# new_boardforfirebot.net
KiCad netlist of a schematic drawn in EAGLE
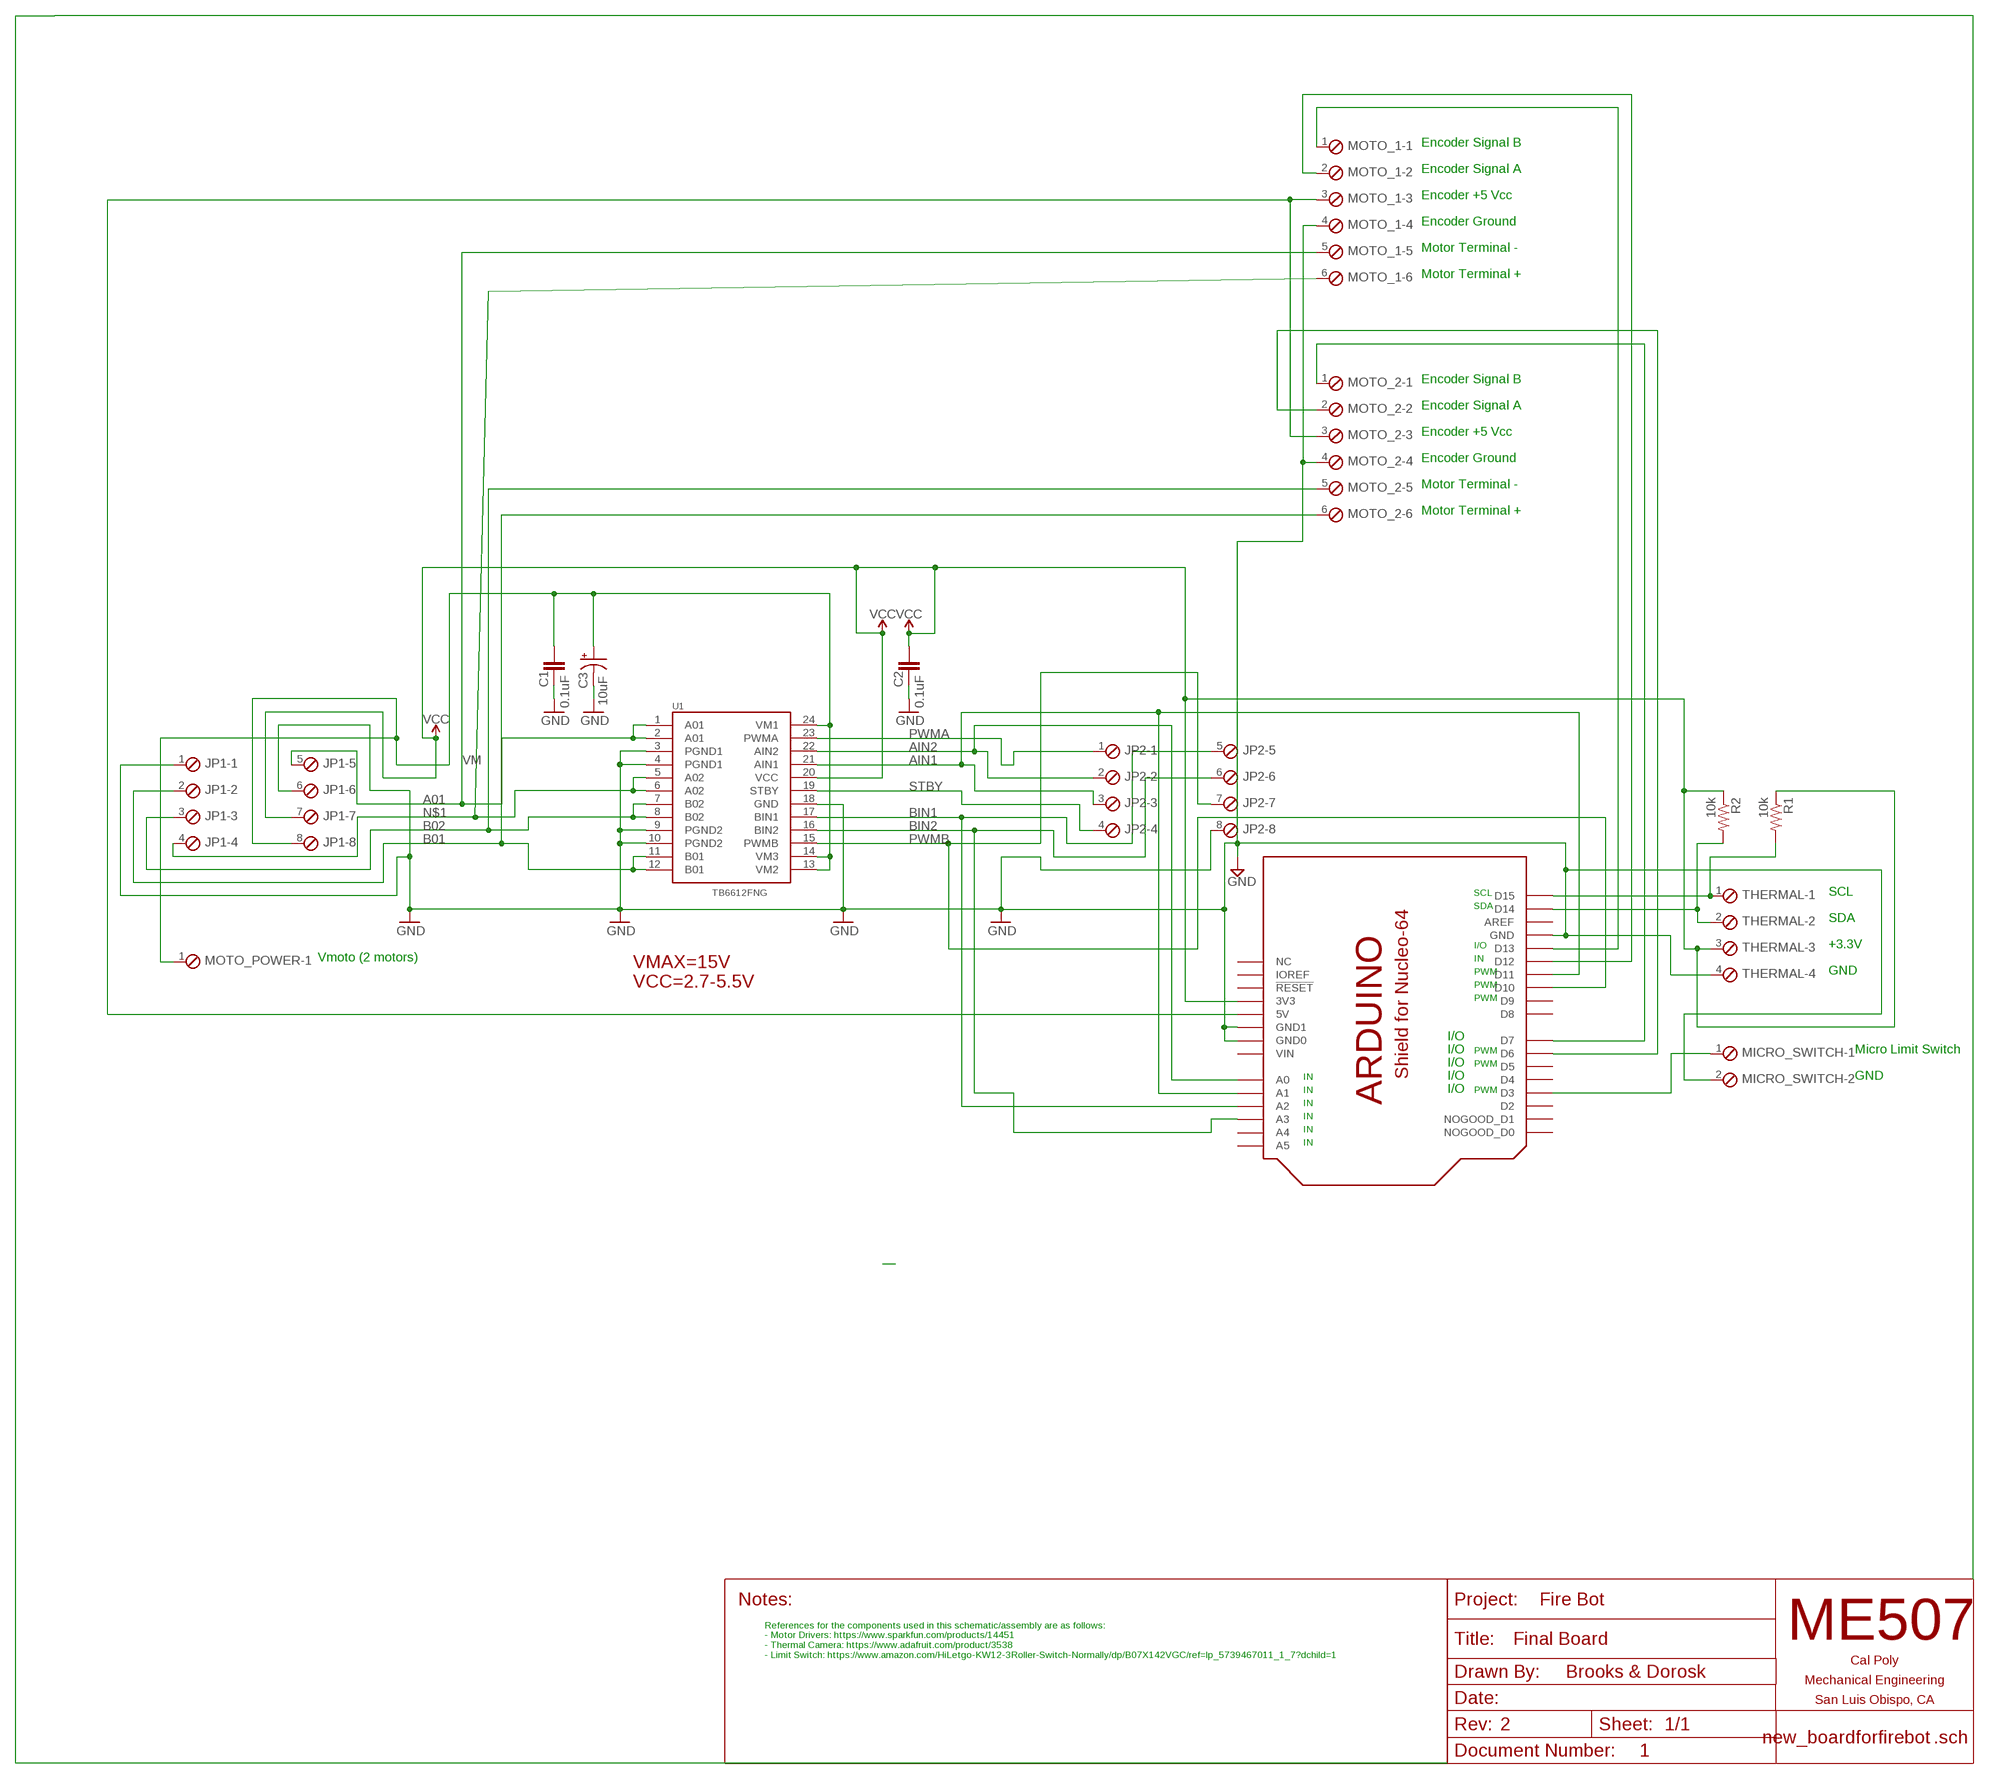
[diagram p0: schematic, sheet 1]

(export (version "E")
  (design (tool "Eeschema 10.0.6"))
  (components
    (comp (ref "C1")
      (value "0.1uF")
      (footprint "eagle-import:0402")
      (libsource (lib "eagle-import") (part "0.1UF-0402-16V-10%"))
    )
    (comp (ref "C2")
      (value "0.1uF")
      (footprint "eagle-import:0402")
      (libsource (lib "eagle-import") (part "0.1UF-0402-16V-10%"))
    )
    (comp (ref "C3")
      (value "10uF")
      (footprint "eagle-import:EIA3528")
      (libsource (lib "eagle-import") (part "10UF-POLAR-EIA3528-20V-10%(TANT)"))
    )
    (comp (ref "JP1")
      (value "SCREWTERM_8P_254")
      (footprint "eagle-import:8POL254")
      (libsource (lib "eagle-import") (part "SCREWTERM_8P_254"))
    )
    (comp (ref "JP2")
      (value "SCREWTERM_8P_254")
      (footprint "eagle-import:8POL254")
      (libsource (lib "eagle-import") (part "SCREWTERM_8P_254"))
    )
    (comp (ref "MICRO_SWITCH")
      (value "SCREWTERM_2P_254")
      (footprint "eagle-import:2POL254")
      (libsource (lib "eagle-import") (part "SCREWTERM_2P_254"))
    )
    (comp (ref "MOTO_1")
      (value "SCREWTERM_6P_254")
      (footprint "eagle-import:6POL254")
      (libsource (lib "eagle-import") (part "SCREWTERM_6P_254"))
    )
    (comp (ref "MOTO_2")
      (value "SCREWTERM_6P_254")
      (footprint "eagle-import:6POL254")
      (libsource (lib "eagle-import") (part "SCREWTERM_6P_254"))
    )
    (comp (ref "MOTO_POWER")
      (value "SCREWTERM_2P_254")
      (footprint "eagle-import:2POL254")
      (libsource (lib "eagle-import") (part "SCREWTERM_2P_254"))
    )
    (comp (ref "R1")
      (value "10k")
      (footprint "eagle-import:R0805")
      (libsource (lib "eagle-import") (part "R-US_R0805"))
    )
    (comp (ref "R2")
      (value "10k")
      (footprint "eagle-import:R0805")
      (libsource (lib "eagle-import") (part "R-US_R0805"))
    )
    (comp (ref "THERMAL")
      (value "SCREWTERM_4P_254")
      (footprint "eagle-import:4POL254")
      (libsource (lib "eagle-import") (part "SCREWTERM_4P_254"))
    )
    (comp (ref "U$1")
      (value "SHIELD_FOR_NUCLE0_64_STANDARD")
      (footprint "eagle-import:SHIELD_FOR_NUCLEO_64_STD")
      (libsource (lib "eagle-import") (part "SHIELD_FOR_NUCLE0_64_STANDARD"))
    )
    (comp (ref "U1")
      (value "TB6612FNG")
      (footprint "eagle-import:SSOP24")
      (libsource (lib "eagle-import") (part "TB6612FNG"))
    )
  )
  (nets
    (net (code "1") (name "/A01") (class "Default")
      (node (ref "JP1") (pin "5") (pinfunction "1_5") (pintype "passive"))
      (node (ref "MOTO_1") (pin "5") (pinfunction "1_5") (pintype "passive"))
      (node (ref "U1") (pin "1") (pinfunction "A01_1") (pintype "bidirectional"))
      (node (ref "U1") (pin "2") (pinfunction "A01_2") (pintype "bidirectional"))
    )
    (net (code "2") (name "/AIN1") (class "Default")
      (node (ref "JP2") (pin "3") (pinfunction "1_3") (pintype "passive"))
      (node (ref "U$1") (pin "A1") (pinfunction "A1_A1") (pintype "bidirectional"))
      (node (ref "U$1") (pin "D11") (pinfunction "D11_D11") (pintype "bidirectional"))
      (node (ref "U1") (pin "21") (pinfunction "AIN1_21") (pintype "bidirectional"))
    )
    (net (code "3") (name "/AIN2") (class "Default")
      (node (ref "JP2") (pin "2") (pinfunction "1_2") (pintype "passive"))
      (node (ref "U$1") (pin "A0") (pinfunction "A0_A0") (pintype "bidirectional"))
      (node (ref "U1") (pin "22") (pinfunction "AIN2_22") (pintype "bidirectional"))
    )
    (net (code "4") (name "/B01") (class "Default")
      (node (ref "JP1") (pin "2") (pinfunction "1_2") (pintype "passive"))
      (node (ref "MOTO_2") (pin "6") (pinfunction "1_6") (pintype "passive"))
      (node (ref "U1") (pin "11") (pinfunction "B01_11") (pintype "bidirectional"))
      (node (ref "U1") (pin "12") (pinfunction "B01_12") (pintype "bidirectional"))
    )
    (net (code "5") (name "/B02") (class "Default")
      (node (ref "JP1") (pin "3") (pinfunction "1_3") (pintype "passive"))
      (node (ref "MOTO_2") (pin "5") (pinfunction "1_5") (pintype "passive"))
      (node (ref "U1") (pin "7") (pinfunction "B02_7") (pintype "bidirectional"))
      (node (ref "U1") (pin "8") (pinfunction "B02_8") (pintype "bidirectional"))
    )
    (net (code "6") (name "/BIN1") (class "Default")
      (node (ref "JP2") (pin "5") (pinfunction "1_5") (pintype "passive"))
      (node (ref "U$1") (pin "A2") (pinfunction "A2_A2") (pintype "bidirectional"))
      (node (ref "U1") (pin "17") (pinfunction "BIN1_17") (pintype "bidirectional"))
    )
    (net (code "7") (name "/BIN2") (class "Default")
      (node (ref "JP2") (pin "6") (pinfunction "1_6") (pintype "passive"))
      (node (ref "U$1") (pin "A3") (pinfunction "A3_A3") (pintype "bidirectional"))
      (node (ref "U1") (pin "16") (pinfunction "BIN2_16") (pintype "bidirectional"))
    )
    (net (code "8") (name "/N$1") (class "Default")
      (node (ref "JP1") (pin "4") (pinfunction "1_4") (pintype "passive"))
      (node (ref "MOTO_1") (pin "6") (pinfunction "1_6") (pintype "passive"))
      (node (ref "U1") (pin "5") (pinfunction "A02_5") (pintype "bidirectional"))
      (node (ref "U1") (pin "6") (pinfunction "A02_6") (pintype "bidirectional"))
    )
    (net (code "9") (name "/PWMA") (class "Default")
      (node (ref "JP2") (pin "1") (pinfunction "1_1") (pintype "passive"))
      (node (ref "U1") (pin "23") (pinfunction "PWMA_23") (pintype "bidirectional"))
    )
    (net (code "10") (name "/PWMB") (class "Default")
      (node (ref "JP2") (pin "7") (pinfunction "1_7") (pintype "passive"))
      (node (ref "U$1") (pin "D10") (pinfunction "D10_D10") (pintype "bidirectional"))
      (node (ref "U1") (pin "15") (pinfunction "PWMB_15") (pintype "bidirectional"))
    )
    (net (code "11") (name "/STBY") (class "Default")
      (node (ref "JP2") (pin "4") (pinfunction "1_4") (pintype "passive"))
      (node (ref "U1") (pin "19") (pinfunction "STBY_19") (pintype "bidirectional"))
    )
    (net (code "12") (name "/VIN") (class "Default")
      (node (ref "U$1") (pin "VIN") (pinfunction "VIN_VIN") (pintype "power_in"))
    )
    (net (code "13") (name "/VM") (class "Default")
      (node (ref "C1") (pin "1") (pinfunction "1_1") (pintype "passive"))
      (node (ref "C3") (pin "A") (pinfunction "+_A") (pintype "passive"))
      (node (ref "JP1") (pin "8") (pinfunction "1_8") (pintype "passive"))
      (node (ref "MOTO_POWER") (pin "1") (pinfunction "1_1") (pintype "passive"))
      (node (ref "U1") (pin "13") (pinfunction "VM2_13") (pintype "bidirectional"))
      (node (ref "U1") (pin "14") (pinfunction "VM3_14") (pintype "bidirectional"))
      (node (ref "U1") (pin "24") (pinfunction "VM1_24") (pintype "bidirectional"))
    )
    (net (code "14") (name "GND") (class "Default")
      (node (ref "C1") (pin "2") (pinfunction "2_2") (pintype "passive"))
      (node (ref "C2") (pin "2") (pinfunction "2_2") (pintype "passive"))
      (node (ref "C3") (pin "C") (pinfunction "-_C") (pintype "passive"))
      (node (ref "JP1") (pin "1") (pinfunction "1_1") (pintype "passive"))
      (node (ref "JP1") (pin "6") (pinfunction "1_6") (pintype "passive"))
      (node (ref "JP2") (pin "8") (pinfunction "1_8") (pintype "passive"))
      (node (ref "MICRO_SWITCH") (pin "2") (pinfunction "1_2") (pintype "passive"))
      (node (ref "MOTO_1") (pin "4") (pinfunction "1_4") (pintype "passive"))
      (node (ref "MOTO_2") (pin "4") (pinfunction "1_4") (pintype "passive"))
      (node (ref "THERMAL") (pin "4") (pinfunction "1_4") (pintype "passive"))
      (node (ref "U$1") (pin "GND") (pinfunction "GND_GND") (pintype "power_in"))
      (node (ref "U$1") (pin "GND1") (pinfunction "GND0_GND1") (pintype "power_in"))
      (node (ref "U$1") (pin "GND2") (pinfunction "GND1_GND2") (pintype "power_in"))
      (node (ref "U1") (pin "10") (pinfunction "PGND2_10") (pintype "bidirectional"))
      (node (ref "U1") (pin "18") (pinfunction "GND_18") (pintype "bidirectional"))
      (node (ref "U1") (pin "3") (pinfunction "PGND1_3") (pintype "bidirectional"))
      (node (ref "U1") (pin "4") (pinfunction "PGND1_4") (pintype "bidirectional"))
      (node (ref "U1") (pin "9") (pinfunction "PGND2_9") (pintype "bidirectional"))
    )
    (net (code "15") (name "Net-(MICRO_SWITCH-Pad1)") (class "Default")
      (node (ref "MICRO_SWITCH") (pin "1") (pinfunction "1_1") (pintype "passive"))
      (node (ref "U$1") (pin "D3") (pinfunction "D3_D3") (pintype "bidirectional"))
    )
    (net (code "16") (name "Net-(MOTO_1-Pad1)") (class "Default")
      (node (ref "MOTO_1") (pin "1") (pinfunction "1_1") (pintype "passive"))
      (node (ref "U$1") (pin "D13") (pinfunction "D13_D13") (pintype "bidirectional"))
    )
    (net (code "17") (name "Net-(MOTO_1B-1)") (class "Default")
      (node (ref "MOTO_1") (pin "2") (pinfunction "1_2") (pintype "passive"))
      (node (ref "U$1") (pin "D12") (pinfunction "D12_D12") (pintype "bidirectional"))
    )
    (net (code "18") (name "Net-(MOTO_1C-1)") (class "Default")
      (node (ref "MOTO_1") (pin "3") (pinfunction "1_3") (pintype "passive"))
      (node (ref "MOTO_2") (pin "3") (pinfunction "1_3") (pintype "passive"))
      (node (ref "U$1") (pin "5V") (pinfunction "5V_5V") (pintype "power_in"))
    )
    (net (code "19") (name "Net-(MOTO_2-Pad1)") (class "Default")
      (node (ref "MOTO_2") (pin "1") (pinfunction "1_1") (pintype "passive"))
      (node (ref "U$1") (pin "D7") (pinfunction "D7_D7") (pintype "bidirectional"))
    )
    (net (code "20") (name "Net-(MOTO_2B-1)") (class "Default")
      (node (ref "MOTO_2") (pin "2") (pinfunction "1_2") (pintype "passive"))
      (node (ref "U$1") (pin "D6") (pinfunction "D6_D6") (pintype "bidirectional"))
    )
    (net (code "21") (name "Net-(R1-Pad2)") (class "Default")
      (node (ref "R1") (pin "2") (pinfunction "2_2") (pintype "passive"))
      (node (ref "THERMAL") (pin "1") (pinfunction "1_1") (pintype "passive"))
      (node (ref "U$1") (pin "D15") (pinfunction "D15_D15") (pintype "bidirectional"))
    )
    (net (code "22") (name "Net-(THERMALB-1)") (class "Default")
      (node (ref "R2") (pin "2") (pinfunction "2_2") (pintype "passive"))
      (node (ref "THERMAL") (pin "2") (pinfunction "1_2") (pintype "passive"))
      (node (ref "U$1") (pin "D14") (pinfunction "D14_D14") (pintype "bidirectional"))
    )
    (net (code "23") (name "VCC") (class "Default")
      (node (ref "C2") (pin "1") (pinfunction "1_1") (pintype "passive"))
      (node (ref "JP1") (pin "7") (pinfunction "1_7") (pintype "passive"))
      (node (ref "R1") (pin "1") (pinfunction "1_1") (pintype "passive"))
      (node (ref "R2") (pin "1") (pinfunction "1_1") (pintype "passive"))
      (node (ref "THERMAL") (pin "3") (pinfunction "1_3") (pintype "passive"))
      (node (ref "U$1") (pin "3V") (pinfunction "3V3_3V") (pintype "power_in"))
      (node (ref "U1") (pin "20") (pinfunction "VCC_20") (pintype "bidirectional"))
    )
    (net (code "24") (name "unconnected-(U$1-NOGOOD_D0-PadD0)") (class "Default")
      (node (ref "U$1") (pin "D0") (pinfunction "NOGOOD_D0_D0") (pintype "no_connect"))
    )
    (net (code "25") (name "unconnected-(U$1-NOGOOD_D1-PadD1)") (class "Default")
      (node (ref "U$1") (pin "D1") (pinfunction "NOGOOD_D1_D1") (pintype "no_connect"))
    )
    (net (code "26") (name "unconnected-(U$1-PadA4)") (class "Default")
      (node (ref "U$1") (pin "A4") (pinfunction "A4_A4") (pintype "bidirectional"))
    )
    (net (code "27") (name "unconnected-(U$1-PadA5)") (class "Default")
      (node (ref "U$1") (pin "A5") (pinfunction "A5_A5") (pintype "bidirectional"))
    )
    (net (code "28") (name "unconnected-(U$1-PadAREF)") (class "Default")
      (node (ref "U$1") (pin "AREF") (pinfunction "AREF_AREF") (pintype "bidirectional"))
    )
    (net (code "29") (name "unconnected-(U$1-PadD2)") (class "Default")
      (node (ref "U$1") (pin "D2") (pinfunction "D2_D2") (pintype "bidirectional"))
    )
    (net (code "30") (name "unconnected-(U$1-PadD4)") (class "Default")
      (node (ref "U$1") (pin "D4") (pinfunction "D4_D4") (pintype "bidirectional"))
    )
    (net (code "31") (name "unconnected-(U$1-PadD5)") (class "Default")
      (node (ref "U$1") (pin "D5") (pinfunction "D5_D5") (pintype "bidirectional"))
    )
    (net (code "32") (name "unconnected-(U$1-PadD8)") (class "Default")
      (node (ref "U$1") (pin "D8") (pinfunction "D8_D8") (pintype "bidirectional"))
    )
    (net (code "33") (name "unconnected-(U$1-PadD9)") (class "Default")
      (node (ref "U$1") (pin "D9") (pinfunction "D9_D9") (pintype "bidirectional"))
    )
    (net (code "34") (name "unconnected-(U$1-PadIOREF)") (class "Default")
      (node (ref "U$1") (pin "IOREF") (pinfunction "IOREF_IOREF") (pintype "bidirectional"))
    )
    (net (code "35") (name "unconnected-(U$1-PadNC)") (class "Default")
      (node (ref "U$1") (pin "NC") (pinfunction "NC_NC") (pintype "no_connect"))
    )
    (net (code "36") (name "unconnected-(U$1-~{RESET}-PadNRST)") (class "Default")
      (node (ref "U$1") (pin "NRST") (pinfunction "~{RESET}_NRST") (pintype "input"))
    )
  )
)
